# ir_sensor.net
KiCad netlist of a schematic drawn in EAGLE
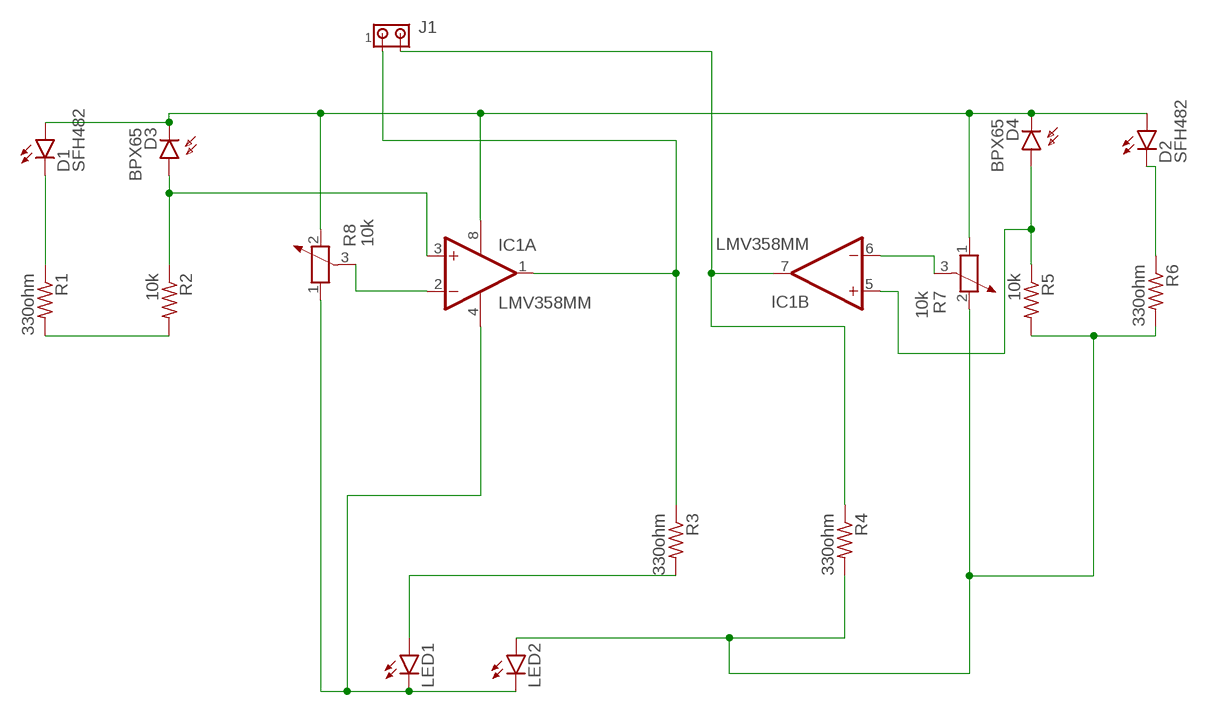
[diagram p0: schematic, sheet 1]

(export (version "E")
  (design (tool "Eeschema 10.0.6"))
  (components
    (comp (ref "D1")
      (value "SFH482")
      (footprint "eagle-import:SFH482")
      (libsource (lib "eagle-import") (part "SFH482"))
    )
    (comp (ref "D2")
      (value "SFH482")
      (footprint "eagle-import:SFH482")
      (libsource (lib "eagle-import") (part "SFH482"))
    )
    (comp (ref "D3")
      (value "BPX65")
      (footprint "eagle-import:BPX65")
      (fields (field (name "MPN") "BPX65."))
      (libsource (lib "eagle-import") (part "BPX65"))
    )
    (comp (ref "D4")
      (value "BPX65")
      (footprint "eagle-import:BPX65")
      (fields (field (name "MPN") "BPX65."))
      (libsource (lib "eagle-import") (part "BPX65"))
    )
    (comp (ref "IC1")
      (value "LMV358MM")
      (footprint "eagle-import:MSOP08")
      (libsource (lib "eagle-import") (part "LMV358?MM"))
    )
    (comp (ref "J1")
      (value "MTA02-100")
      (footprint "eagle-import:10X02MTA")
      (libsource (lib "eagle-import") (part "MTA02-100"))
    )
    (comp (ref "LED1")
      (value "LED3MM")
      (footprint "eagle-import:LED3MM")
      (libsource (lib "eagle-import") (part "LED3MM"))
    )
    (comp (ref "LED2")
      (value "LED3MM")
      (footprint "eagle-import:LED3MM")
      (libsource (lib "eagle-import") (part "LED3MM"))
    )
    (comp (ref "R1")
      (value "330ohm")
      (footprint "eagle-import:0207_10")
      (libsource (lib "eagle-import") (part "R-US_0207/10"))
    )
    (comp (ref "R2")
      (value "10k")
      (footprint "eagle-import:0207_10")
      (libsource (lib "eagle-import") (part "R-US_0207/10"))
    )
    (comp (ref "R3")
      (value "330ohm")
      (footprint "eagle-import:0207_10")
      (libsource (lib "eagle-import") (part "R-US_0207/10"))
    )
    (comp (ref "R4")
      (value "330ohm")
      (footprint "eagle-import:0207_10")
      (libsource (lib "eagle-import") (part "R-US_0207/10"))
    )
    (comp (ref "R5")
      (value "10k")
      (footprint "eagle-import:0207_10")
      (libsource (lib "eagle-import") (part "R-US_0207/10"))
    )
    (comp (ref "R6")
      (value "330ohm")
      (footprint "eagle-import:0207_10")
      (libsource (lib "eagle-import") (part "R-US_0207/10"))
    )
    (comp (ref "R7")
      (value "10k")
      (footprint "eagle-import:PT-10")
      (libsource (lib "eagle-import") (part "POTENTIOMETER_PT-10"))
    )
    (comp (ref "R8")
      (value "10k")
      (footprint "eagle-import:PT-10")
      (libsource (lib "eagle-import") (part "POTENTIOMETER_PT-10"))
    )
  )
  (nets
    (net (code "1") (name "Net-(D1-C)") (class "Default")
      (node (ref "D1") (pin "K") (pinfunction "C_K") (pintype "passive"))
      (node (ref "R1") (pin "1") (pinfunction "1_1") (pintype "passive"))
    )
    (net (code "2") (name "Net-(D2-C)") (class "Default")
      (node (ref "D2") (pin "K") (pinfunction "C_K") (pintype "passive"))
      (node (ref "R6") (pin "1") (pinfunction "1_1") (pintype "passive"))
    )
    (net (code "3") (name "Net-(D3-C)") (class "Default")
      (node (ref "D1") (pin "A") (pinfunction "A_A") (pintype "passive"))
      (node (ref "D2") (pin "A") (pinfunction "A_A") (pintype "passive"))
      (node (ref "D3") (pin "K") (pinfunction "C_K") (pintype "passive"))
      (node (ref "D4") (pin "K") (pinfunction "C_K") (pintype "passive"))
      (node (ref "IC1") (pin "8") (pinfunction "V+_8") (pintype "power_in"))
      (node (ref "R7") (pin "1") (pinfunction "1_1") (pintype "passive"))
      (node (ref "R8") (pin "2") (pinfunction "2_2") (pintype "passive"))
    )
    (net (code "4") (name "Net-(IC1A-+IN)") (class "Default")
      (node (ref "D3") (pin "A") (pinfunction "A_A") (pintype "passive"))
      (node (ref "IC1") (pin "3") (pinfunction "+IN_3") (pintype "input"))
      (node (ref "R2") (pin "1") (pinfunction "1_1") (pintype "passive"))
    )
    (net (code "5") (name "Net-(IC1A--IN)") (class "Default")
      (node (ref "IC1") (pin "2") (pinfunction "-IN_2") (pintype "input"))
      (node (ref "R8") (pin "3") (pinfunction "3_3") (pintype "passive"))
    )
    (net (code "6") (name "Net-(IC1A-OUT)") (class "Default")
      (node (ref "IC1") (pin "1") (pinfunction "OUT_1") (pintype "output"))
      (node (ref "J1") (pin "1") (pinfunction "1_1") (pintype "passive"))
      (node (ref "R3") (pin "1") (pinfunction "1_1") (pintype "passive"))
    )
    (net (code "7") (name "Net-(IC1B-+IN)") (class "Default")
      (node (ref "D4") (pin "A") (pinfunction "A_A") (pintype "passive"))
      (node (ref "IC1") (pin "5") (pinfunction "+IN_5") (pintype "input"))
      (node (ref "R5") (pin "1") (pinfunction "1_1") (pintype "passive"))
    )
    (net (code "8") (name "Net-(IC1B--IN)") (class "Default")
      (node (ref "IC1") (pin "6") (pinfunction "-IN_6") (pintype "input"))
      (node (ref "R7") (pin "3") (pinfunction "3_3") (pintype "passive"))
    )
    (net (code "9") (name "Net-(IC1B-OUT)") (class "Default")
      (node (ref "IC1") (pin "7") (pinfunction "OUT_7") (pintype "output"))
      (node (ref "J1") (pin "2") (pinfunction "2_2") (pintype "passive"))
      (node (ref "R4") (pin "1") (pinfunction "1_1") (pintype "passive"))
    )
    (net (code "10") (name "Net-(IC1C-V-)") (class "Default")
      (node (ref "IC1") (pin "4") (pinfunction "V-_4") (pintype "power_in"))
      (node (ref "LED1") (pin "K") (pinfunction "C_K") (pintype "passive"))
      (node (ref "LED2") (pin "K") (pinfunction "C_K") (pintype "passive"))
      (node (ref "R8") (pin "1") (pinfunction "1_1") (pintype "passive"))
    )
    (net (code "11") (name "Net-(LED1-PadA)") (class "Default")
      (node (ref "LED1") (pin "A") (pinfunction "A_A") (pintype "passive"))
      (node (ref "R3") (pin "2") (pinfunction "2_2") (pintype "passive"))
    )
    (net (code "12") (name "Net-(LED2-PadA)") (class "Default")
      (node (ref "LED2") (pin "A") (pinfunction "A_A") (pintype "passive"))
      (node (ref "R4") (pin "2") (pinfunction "2_2") (pintype "passive"))
      (node (ref "R5") (pin "2") (pinfunction "2_2") (pintype "passive"))
      (node (ref "R6") (pin "2") (pinfunction "2_2") (pintype "passive"))
      (node (ref "R7") (pin "2") (pinfunction "2_2") (pintype "passive"))
    )
    (net (code "13") (name "Net-(R1-Pad2)") (class "Default")
      (node (ref "R1") (pin "2") (pinfunction "2_2") (pintype "passive"))
      (node (ref "R2") (pin "2") (pinfunction "2_2") (pintype "passive"))
    )
  )
)
